# Interface_RS232.net
KiCad netlist of a schematic drawn in Altium Designer
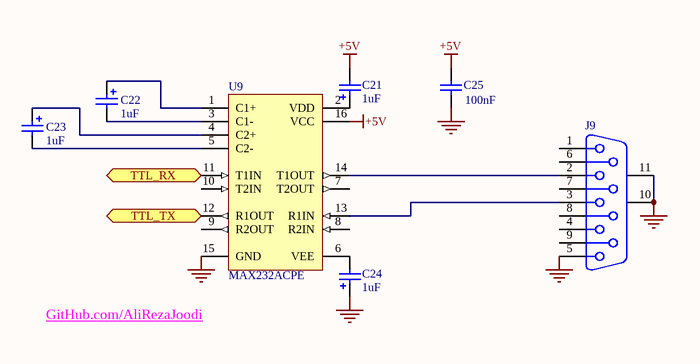
[diagram p0: Interface_RS232.SchDoc]

(export (version "E")
  (design (tool "Eeschema 10.0.6"))
  (components
    (comp (ref "C21")
      (value "1uF")
      (footprint "CAPPR2.5-6.3x5")
      (description "Polarized Capacitor (Radial)")
      (fields
        (field (name "MANUFACTURER") "Generic Components")
        (field (name "Comment") "C18")
        (field (name "PUBLISHER") "Altium Limited")
      )
      (libsource (lib "Miscellaneous Devices") (part "Cap Pol1"))
    )
    (comp (ref "C22")
      (value "1uF")
      (footprint "CAPPR2.5-6.3x5")
      (description "Polarized Capacitor (Radial)")
      (fields
        (field (name "MANUFACTURER") "Generic Components")
        (field (name "Comment") "C18")
        (field (name "PUBLISHER") "Altium Limited")
      )
      (libsource (lib "Miscellaneous Devices") (part "Cap Pol1"))
    )
    (comp (ref "C23")
      (value "1uF")
      (footprint "CAPPR2.5-6.3x5")
      (description "Polarized Capacitor (Radial)")
      (fields
        (field (name "MANUFACTURER") "Generic Components")
        (field (name "Comment") "C18")
        (field (name "PUBLISHER") "Altium Limited")
      )
      (libsource (lib "Miscellaneous Devices") (part "Cap Pol1"))
    )
    (comp (ref "C24")
      (value "1uF")
      (footprint "CAPPR2.5-6.3x5")
      (description "Polarized Capacitor (Radial)")
      (fields
        (field (name "MANUFACTURER") "Generic Components")
        (field (name "Comment") "C18")
        (field (name "PUBLISHER") "Altium Limited")
      )
      (libsource (lib "Miscellaneous Devices") (part "Cap Pol1"))
    )
    (comp (ref "C25")
      (value "100nF")
      (footprint "CAPNTO2.54-3.05x1.78A")
      (description "Capacitor")
      (fields (field (name "Comment") "Cap") (field (name "PUBLISHER") "Altium Limited"))
      (libsource (lib "Miscellaneous Devices") (part "Cap"))
    )
    (comp (ref "J9")
      (value "D Connector 9")
      (footprint "DSUB1.385-2H9")
      (description "Receptacle Assembly, 9 Position, Right Angle")
      (fields (field (name "MANUFACTURER") "Generic Components") (field (name "PUBLISHER") "Altium Limited"))
      (libsource (lib "Miscellaneous Connectors") (part "D Connector 9"))
    )
    (comp (ref "U9")
      (value "MAX232ACPE")
      (footprint "PE16A")
      (description "+5V Powered, Multi-Channel RS-232 Driver/Receiver")
      (fields (field (name "PUBLISHER") "Altium Limited"))
      (libsource (lib "Maxim Communication Transceiver") (part "MAX232ACPE"))
    )
  )
  (nets
    (net (code "1") (name "+5V") (class "Default")
      (node (ref "C21") (pin "2") (pinfunction "2_2") (pintype "passive"))
      (node (ref "C25") (pin "1") (pinfunction "1_1") (pintype "passive"))
      (node (ref "U9") (pin "16") (pinfunction "VCC_16") (pintype "power_in"))
    )
    (net (code "2") (name "/TTL_RX") (class "Default")
      (node (ref "U9") (pin "11") (pinfunction "T1IN_11") (pintype "input"))
    )
    (net (code "3") (name "/TTL_TX") (class "Default")
      (node (ref "U9") (pin "12") (pinfunction "R1OUT_12") (pintype "output"))
    )
    (net (code "4") (name "GND") (class "Default")
      (node (ref "C24") (pin "1") (pinfunction "1_1") (pintype "passive"))
      (node (ref "C25") (pin "2") (pinfunction "2_2") (pintype "passive"))
      (node (ref "J9") (pin "10") (pinfunction "MH1_10") (pintype "passive"))
      (node (ref "J9") (pin "11") (pinfunction "MH2_11") (pintype "passive"))
      (node (ref "J9") (pin "5") (pinfunction "5_5") (pintype "passive"))
      (node (ref "U9") (pin "15") (pinfunction "GND_15") (pintype "power_in"))
    )
    (net (code "5") (name "Net-(U9-C1+)") (class "Default")
      (node (ref "C22") (pin "1") (pinfunction "1_1") (pintype "passive"))
      (node (ref "U9") (pin "1") (pinfunction "C1+_1") (pintype "passive"))
    )
    (net (code "6") (name "Net-(U9-C1-)") (class "Default")
      (node (ref "C22") (pin "2") (pinfunction "2_2") (pintype "passive"))
      (node (ref "U9") (pin "3") (pinfunction "C1-_3") (pintype "passive"))
    )
    (net (code "7") (name "Net-(U9-C2+)") (class "Default")
      (node (ref "C23") (pin "1") (pinfunction "1_1") (pintype "passive"))
      (node (ref "U9") (pin "4") (pinfunction "C2+_4") (pintype "passive"))
    )
    (net (code "8") (name "Net-(U9-C2-)") (class "Default")
      (node (ref "C23") (pin "2") (pinfunction "2_2") (pintype "passive"))
      (node (ref "U9") (pin "5") (pinfunction "C2-_5") (pintype "passive"))
    )
    (net (code "9") (name "Net-(U9-R1IN)") (class "Default")
      (node (ref "J9") (pin "3") (pinfunction "3_3") (pintype "passive"))
      (node (ref "U9") (pin "13") (pinfunction "R1IN_13") (pintype "input"))
    )
    (net (code "10") (name "Net-(U9-T1OUT)") (class "Default")
      (node (ref "J9") (pin "2") (pinfunction "2_2") (pintype "passive"))
      (node (ref "U9") (pin "14") (pinfunction "T1OUT_14") (pintype "output"))
    )
    (net (code "11") (name "Net-(U9-VDD)") (class "Default")
      (node (ref "C21") (pin "1") (pinfunction "1_1") (pintype "passive"))
      (node (ref "U9") (pin "2") (pinfunction "VDD_2") (pintype "power_in"))
    )
    (net (code "12") (name "Net-(U9-VEE)") (class "Default")
      (node (ref "C24") (pin "2") (pinfunction "2_2") (pintype "passive"))
      (node (ref "U9") (pin "6") (pinfunction "VEE_6") (pintype "power_in"))
    )
    (net (code "13") (name "unconnected-(J9-Pad1)") (class "Default")
      (node (ref "J9") (pin "1") (pinfunction "1_1") (pintype "passive"))
    )
    (net (code "14") (name "unconnected-(J9-Pad4)") (class "Default")
      (node (ref "J9") (pin "4") (pinfunction "4_4") (pintype "passive"))
    )
    (net (code "15") (name "unconnected-(J9-Pad6)") (class "Default")
      (node (ref "J9") (pin "6") (pinfunction "6_6") (pintype "passive"))
    )
    (net (code "16") (name "unconnected-(J9-Pad7)") (class "Default")
      (node (ref "J9") (pin "7") (pinfunction "7_7") (pintype "passive"))
    )
    (net (code "17") (name "unconnected-(J9-Pad8)") (class "Default")
      (node (ref "J9") (pin "8") (pinfunction "8_8") (pintype "passive"))
    )
    (net (code "18") (name "unconnected-(J9-Pad9)") (class "Default")
      (node (ref "J9") (pin "9") (pinfunction "9_9") (pintype "passive"))
    )
    (net (code "19") (name "unconnected-(U9-R2IN-Pad8)") (class "Default")
      (node (ref "U9") (pin "8") (pinfunction "R2IN_8") (pintype "input"))
    )
    (net (code "20") (name "unconnected-(U9-R2OUT-Pad9)") (class "Default")
      (node (ref "U9") (pin "9") (pinfunction "R2OUT_9") (pintype "output"))
    )
    (net (code "21") (name "unconnected-(U9-T2IN-Pad10)") (class "Default")
      (node (ref "U9") (pin "10") (pinfunction "T2IN_10") (pintype "input"))
    )
    (net (code "22") (name "unconnected-(U9-T2OUT-Pad7)") (class "Default")
      (node (ref "U9") (pin "7") (pinfunction "T2OUT_7") (pintype "output"))
    )
  )
)
